# vendotron5000_v1.net
KiCad netlist of a schematic drawn in EAGLE
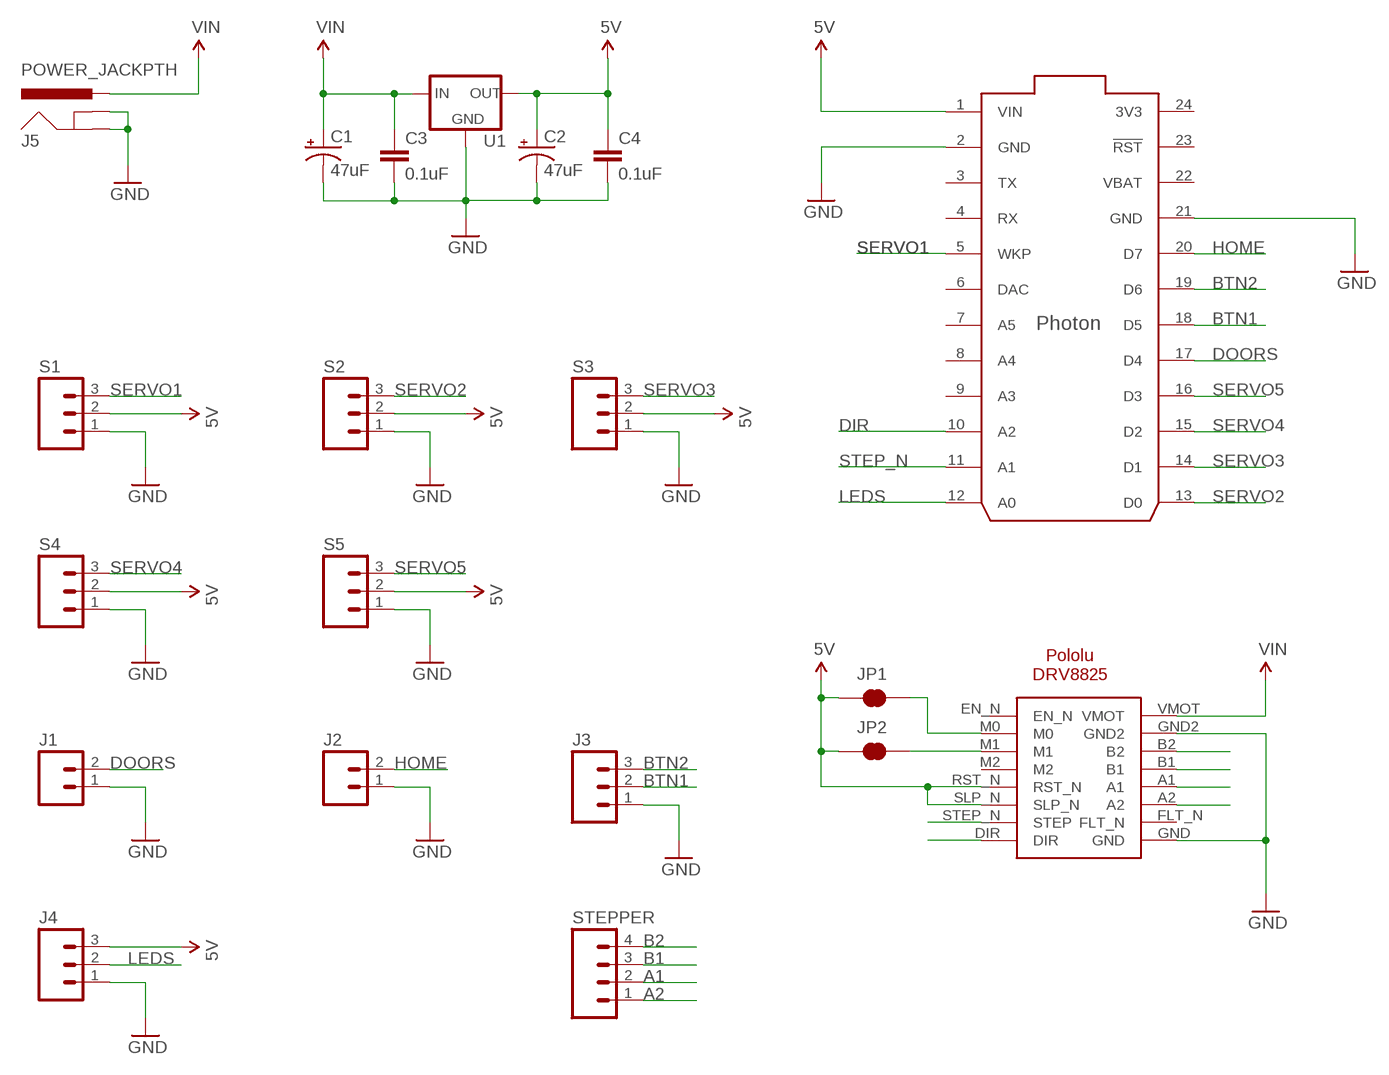
[diagram p0: schematic, sheet 1]

(export (version "E")
  (design (tool "Eeschema 10.0.6"))
  (components
    (comp (ref "C1")
      (value "47uF")
      (footprint "eagle-import:CPOL-RADIAL-10UF-25V")
      (libsource (lib "eagle-import") (part "CAP_POLPTH2"))
    )
    (comp (ref "C2")
      (value "47uF")
      (footprint "eagle-import:CPOL-RADIAL-10UF-25V")
      (libsource (lib "eagle-import") (part "CAP_POLPTH2"))
    )
    (comp (ref "C3")
      (value "0.1uF")
      (footprint "eagle-import:CAP-PTH-SMALL")
      (libsource (lib "eagle-import") (part "CAPPTH"))
    )
    (comp (ref "C4")
      (value "0.1uF")
      (footprint "eagle-import:CAP-PTH-SMALL")
      (libsource (lib "eagle-import") (part "CAPPTH"))
    )
    (comp (ref "J1")
      (value "M023.5MM")
      (footprint "eagle-import:SCREWTERMINAL-3.5MM-2")
      (libsource (lib "eagle-import") (part "M023.5MM"))
    )
    (comp (ref "J2")
      (value "M023.5MM")
      (footprint "eagle-import:SCREWTERMINAL-3.5MM-2")
      (libsource (lib "eagle-import") (part "M023.5MM"))
    )
    (comp (ref "J3")
      (value "M03SCREW")
      (footprint "eagle-import:SCREWTERMINAL-3.5MM-3")
      (libsource (lib "eagle-import") (part "M03SCREW"))
    )
    (comp (ref "J4")
      (value "M03SCREW")
      (footprint "eagle-import:SCREWTERMINAL-3.5MM-3")
      (libsource (lib "eagle-import") (part "M03SCREW"))
    )
    (comp (ref "J5")
      (value "POWER_JACKPTH")
      (footprint "eagle-import:POWER_JACK_PTH")
      (libsource (lib "eagle-import") (part "POWER_JACKPTH"))
    )
    (comp (ref "JP1")
      (value "JUMPER-PAD-2-NC_BY_TRACE")
      (footprint "eagle-import:PAD-JUMPER-2-NC_BY_TRACE_YES_SILK")
      (libsource (lib "eagle-import") (part "JUMPER-PAD-2-NC_BY_TRACE"))
    )
    (comp (ref "JP2")
      (value "JUMPER-PAD-2-NC_BY_TRACE")
      (footprint "eagle-import:PAD-JUMPER-2-NC_BY_TRACE_YES_SILK")
      (libsource (lib "eagle-import") (part "JUMPER-PAD-2-NC_BY_TRACE"))
    )
    (comp (ref "S1")
      (value "M03PTH")
      (footprint "eagle-import:1X03")
      (libsource (lib "eagle-import") (part "M03PTH"))
    )
    (comp (ref "S2")
      (value "M03PTH")
      (footprint "eagle-import:1X03")
      (libsource (lib "eagle-import") (part "M03PTH"))
    )
    (comp (ref "S3")
      (value "M03PTH")
      (footprint "eagle-import:1X03")
      (libsource (lib "eagle-import") (part "M03PTH"))
    )
    (comp (ref "S4")
      (value "M03PTH")
      (footprint "eagle-import:1X03")
      (libsource (lib "eagle-import") (part "M03PTH"))
    )
    (comp (ref "S5")
      (value "M03PTH")
      (footprint "eagle-import:1X03")
      (libsource (lib "eagle-import") (part "M03PTH"))
    )
    (comp (ref "STEPPER")
      (value "M04SCREW")
      (footprint "eagle-import:SCREWTERMINAL-3.5MM-4")
      (libsource (lib "eagle-import") (part "M04SCREW"))
    )
    (comp (ref "U$1")
      (value "PHOTON_WITH_HEADERS")
      (footprint "eagle-import:PHOTON")
      (libsource (lib "eagle-import") (part "PHOTON_WITH_HEADERS"))
    )
    (comp (ref "U$2")
      (value "POLOLU-DRV8825")
      (footprint "eagle-import:POLOLU-DRV8825")
      (libsource (lib "eagle-import") (part "POLOLU-DRV8825"))
    )
    (comp (ref "U1")
      (value "V_REG_78XXSINK")
      (footprint "eagle-import:TO220-IGO")
      (libsource (lib "eagle-import") (part "V_REG_78XXSINK"))
    )
  )
  (nets
    (net (code "1") (name "/3V3") (class "Default")
      (node (ref "U$1") (pin "24") (pinfunction "3V3_24") (pintype "power_in"))
    )
    (net (code "2") (name "/A1") (class "Default")
      (node (ref "STEPPER") (pin "2") (pinfunction "2_2") (pintype "passive"))
      (node (ref "U$2") (pin "A1") (pinfunction "A1_A1") (pintype "bidirectional"))
    )
    (net (code "3") (name "/A2") (class "Default")
      (node (ref "STEPPER") (pin "1") (pinfunction "1_1") (pintype "passive"))
      (node (ref "U$2") (pin "A2") (pinfunction "A2_A2") (pintype "bidirectional"))
    )
    (net (code "4") (name "/B1") (class "Default")
      (node (ref "STEPPER") (pin "3") (pinfunction "3_3") (pintype "passive"))
      (node (ref "U$2") (pin "B1") (pinfunction "B1_B1") (pintype "bidirectional"))
    )
    (net (code "5") (name "/B2") (class "Default")
      (node (ref "STEPPER") (pin "4") (pinfunction "4_4") (pintype "passive"))
      (node (ref "U$2") (pin "B2") (pinfunction "B2_B2") (pintype "bidirectional"))
    )
    (net (code "6") (name "/BTN1") (class "Default")
      (node (ref "J3") (pin "2") (pinfunction "2_2") (pintype "passive"))
      (node (ref "U$1") (pin "18") (pinfunction "D5_18") (pintype "bidirectional"))
    )
    (net (code "7") (name "/BTN2") (class "Default")
      (node (ref "J3") (pin "3") (pinfunction "3_3") (pintype "passive"))
      (node (ref "U$1") (pin "19") (pinfunction "D6_19") (pintype "bidirectional"))
    )
    (net (code "8") (name "/DIR") (class "Default")
      (node (ref "U$1") (pin "10") (pinfunction "A2_10") (pintype "bidirectional"))
      (node (ref "U$2") (pin "DIR") (pinfunction "DIR_DIR") (pintype "bidirectional"))
    )
    (net (code "9") (name "/DOORS") (class "Default")
      (node (ref "J1") (pin "2") (pinfunction "2_2") (pintype "passive"))
      (node (ref "U$1") (pin "17") (pinfunction "D4_17") (pintype "bidirectional"))
    )
    (net (code "10") (name "/HOME") (class "Default")
      (node (ref "J2") (pin "2") (pinfunction "2_2") (pintype "passive"))
      (node (ref "U$1") (pin "20") (pinfunction "D7_20") (pintype "bidirectional"))
    )
    (net (code "11") (name "/LEDS") (class "Default")
      (node (ref "J4") (pin "2") (pinfunction "2_2") (pintype "passive"))
      (node (ref "U$1") (pin "12") (pinfunction "A0_12") (pintype "bidirectional"))
    )
    (net (code "12") (name "/SERVO1") (class "Default")
      (node (ref "S1") (pin "3") (pinfunction "3_3") (pintype "passive"))
      (node (ref "U$1") (pin "5") (pinfunction "WKP_5") (pintype "bidirectional"))
    )
    (net (code "13") (name "/SERVO2") (class "Default")
      (node (ref "S2") (pin "3") (pinfunction "3_3") (pintype "passive"))
      (node (ref "U$1") (pin "13") (pinfunction "D0_13") (pintype "bidirectional"))
    )
    (net (code "14") (name "/SERVO3") (class "Default")
      (node (ref "S3") (pin "3") (pinfunction "3_3") (pintype "passive"))
      (node (ref "U$1") (pin "14") (pinfunction "D1_14") (pintype "bidirectional"))
    )
    (net (code "15") (name "/SERVO4") (class "Default")
      (node (ref "S4") (pin "3") (pinfunction "3_3") (pintype "passive"))
      (node (ref "U$1") (pin "15") (pinfunction "D2_15") (pintype "bidirectional"))
    )
    (net (code "16") (name "/SERVO5") (class "Default")
      (node (ref "S5") (pin "3") (pinfunction "3_3") (pintype "passive"))
      (node (ref "U$1") (pin "16") (pinfunction "D3_16") (pintype "bidirectional"))
    )
    (net (code "17") (name "/STEP_N") (class "Default")
      (node (ref "U$1") (pin "11") (pinfunction "A1_11") (pintype "bidirectional"))
      (node (ref "U$2") (pin "STEP_N") (pinfunction "STEP_STEP_N") (pintype "bidirectional"))
    )
    (net (code "18") (name "/VBAT") (class "Default")
      (node (ref "U$1") (pin "22") (pinfunction "VBAT_22") (pintype "power_in"))
    )
    (net (code "19") (name "5V") (class "Default")
      (node (ref "C2") (pin "1") (pinfunction "+_1") (pintype "passive"))
      (node (ref "C4") (pin "1") (pinfunction "1_1") (pintype "passive"))
      (node (ref "J4") (pin "3") (pinfunction "3_3") (pintype "passive"))
      (node (ref "JP1") (pin "1") (pinfunction "1_1") (pintype "passive"))
      (node (ref "JP2") (pin "1") (pinfunction "1_1") (pintype "passive"))
      (node (ref "S1") (pin "2") (pinfunction "2_2") (pintype "passive"))
      (node (ref "S2") (pin "2") (pinfunction "2_2") (pintype "passive"))
      (node (ref "S3") (pin "2") (pinfunction "2_2") (pintype "passive"))
      (node (ref "S4") (pin "2") (pinfunction "2_2") (pintype "passive"))
      (node (ref "S5") (pin "2") (pinfunction "2_2") (pintype "passive"))
      (node (ref "U$1") (pin "1") (pinfunction "VIN_1") (pintype "power_in"))
      (node (ref "U$2") (pin "RST_N") (pinfunction "RST_N_RST_N") (pintype "bidirectional"))
      (node (ref "U$2") (pin "SLP_N") (pinfunction "SLP_N_SLP_N") (pintype "bidirectional"))
      (node (ref "U1") (pin "OUT") (pinfunction "OUT_OUT") (pintype "passive"))
    )
    (net (code "20") (name "GND") (class "Default")
      (node (ref "C1") (pin "2") (pinfunction "-_2") (pintype "passive"))
      (node (ref "C2") (pin "2") (pinfunction "-_2") (pintype "passive"))
      (node (ref "C3") (pin "2") (pinfunction "2_2") (pintype "passive"))
      (node (ref "C4") (pin "2") (pinfunction "2_2") (pintype "passive"))
      (node (ref "J1") (pin "1") (pinfunction "1_1") (pintype "passive"))
      (node (ref "J2") (pin "1") (pinfunction "1_1") (pintype "passive"))
      (node (ref "J3") (pin "1") (pinfunction "1_1") (pintype "passive"))
      (node (ref "J4") (pin "1") (pinfunction "1_1") (pintype "passive"))
      (node (ref "J5") (pin "GND") (pinfunction "GND_GND") (pintype "bidirectional"))
      (node (ref "J5") (pin "GNDBREAK") (pinfunction "GNDBREAK_GNDBREAK") (pintype "bidirectional"))
      (node (ref "S1") (pin "1") (pinfunction "1_1") (pintype "passive"))
      (node (ref "S2") (pin "1") (pinfunction "1_1") (pintype "passive"))
      (node (ref "S3") (pin "1") (pinfunction "1_1") (pintype "passive"))
      (node (ref "S4") (pin "1") (pinfunction "1_1") (pintype "passive"))
      (node (ref "S5") (pin "1") (pinfunction "1_1") (pintype "passive"))
      (node (ref "U$1") (pin "2") (pinfunction "GND_2") (pintype "power_in"))
      (node (ref "U$1") (pin "21") (pinfunction "GND_21") (pintype "power_in"))
      (node (ref "U$2") (pin "GND") (pinfunction "GND_GND") (pintype "bidirectional"))
      (node (ref "U$2") (pin "GND2") (pinfunction "GND2_GND2") (pintype "bidirectional"))
      (node (ref "U1") (pin "GND") (pinfunction "GND_GND") (pintype "input"))
    )
    (net (code "21") (name "Net-(JP1-Pad2)") (class "Default")
      (node (ref "JP1") (pin "2") (pinfunction "2_2") (pintype "passive"))
      (node (ref "U$2") (pin "M0") (pinfunction "M0_M0") (pintype "bidirectional"))
    )
    (net (code "22") (name "Net-(JP2-Pad2)") (class "Default")
      (node (ref "JP2") (pin "2") (pinfunction "2_2") (pintype "passive"))
      (node (ref "U$2") (pin "M1") (pinfunction "M1_M1") (pintype "bidirectional"))
    )
    (net (code "23") (name "VIN") (class "Default")
      (node (ref "C1") (pin "1") (pinfunction "+_1") (pintype "passive"))
      (node (ref "C3") (pin "1") (pinfunction "1_1") (pintype "passive"))
      (node (ref "J5") (pin "PWR") (pinfunction "PWR_PWR") (pintype "bidirectional"))
      (node (ref "U$2") (pin "VMOT") (pinfunction "VMOT_VMOT") (pintype "bidirectional"))
      (node (ref "U1") (pin "IN") (pinfunction "IN_IN") (pintype "input"))
    )
    (net (code "24") (name "unconnected-(U$1-A3-Pad9)") (class "Default")
      (node (ref "U$1") (pin "9") (pinfunction "A3_9") (pintype "bidirectional"))
    )
    (net (code "25") (name "unconnected-(U$1-A4-Pad8)") (class "Default")
      (node (ref "U$1") (pin "8") (pinfunction "A4_8") (pintype "bidirectional"))
    )
    (net (code "26") (name "unconnected-(U$1-A5-Pad7)") (class "Default")
      (node (ref "U$1") (pin "7") (pinfunction "A5_7") (pintype "bidirectional"))
    )
    (net (code "27") (name "unconnected-(U$1-DAC-Pad6)") (class "Default")
      (node (ref "U$1") (pin "6") (pinfunction "DAC_6") (pintype "bidirectional"))
    )
    (net (code "28") (name "unconnected-(U$1-RX-Pad4)") (class "Default")
      (node (ref "U$1") (pin "4") (pinfunction "RX_4") (pintype "bidirectional"))
    )
    (net (code "29") (name "unconnected-(U$1-TX-Pad3)") (class "Default")
      (node (ref "U$1") (pin "3") (pinfunction "TX_3") (pintype "bidirectional"))
    )
    (net (code "30") (name "unconnected-(U$1-~{RST}-Pad23)") (class "Default")
      (node (ref "U$1") (pin "23") (pinfunction "~{RST}_23") (pintype "bidirectional"))
    )
    (net (code "31") (name "unconnected-(U$2-PadEN_N)") (class "Default")
      (node (ref "U$2") (pin "EN_N") (pinfunction "EN_N_EN_N") (pintype "bidirectional"))
    )
    (net (code "32") (name "unconnected-(U$2-PadFLT_N)") (class "Default")
      (node (ref "U$2") (pin "FLT_N") (pinfunction "FLT_N_FLT_N") (pintype "bidirectional"))
    )
    (net (code "33") (name "unconnected-(U$2-PadM2)") (class "Default")
      (node (ref "U$2") (pin "M2") (pinfunction "M2_M2") (pintype "bidirectional"))
    )
  )
)
